# Connector.net
KiCad netlist of a schematic drawn in Altium Designer
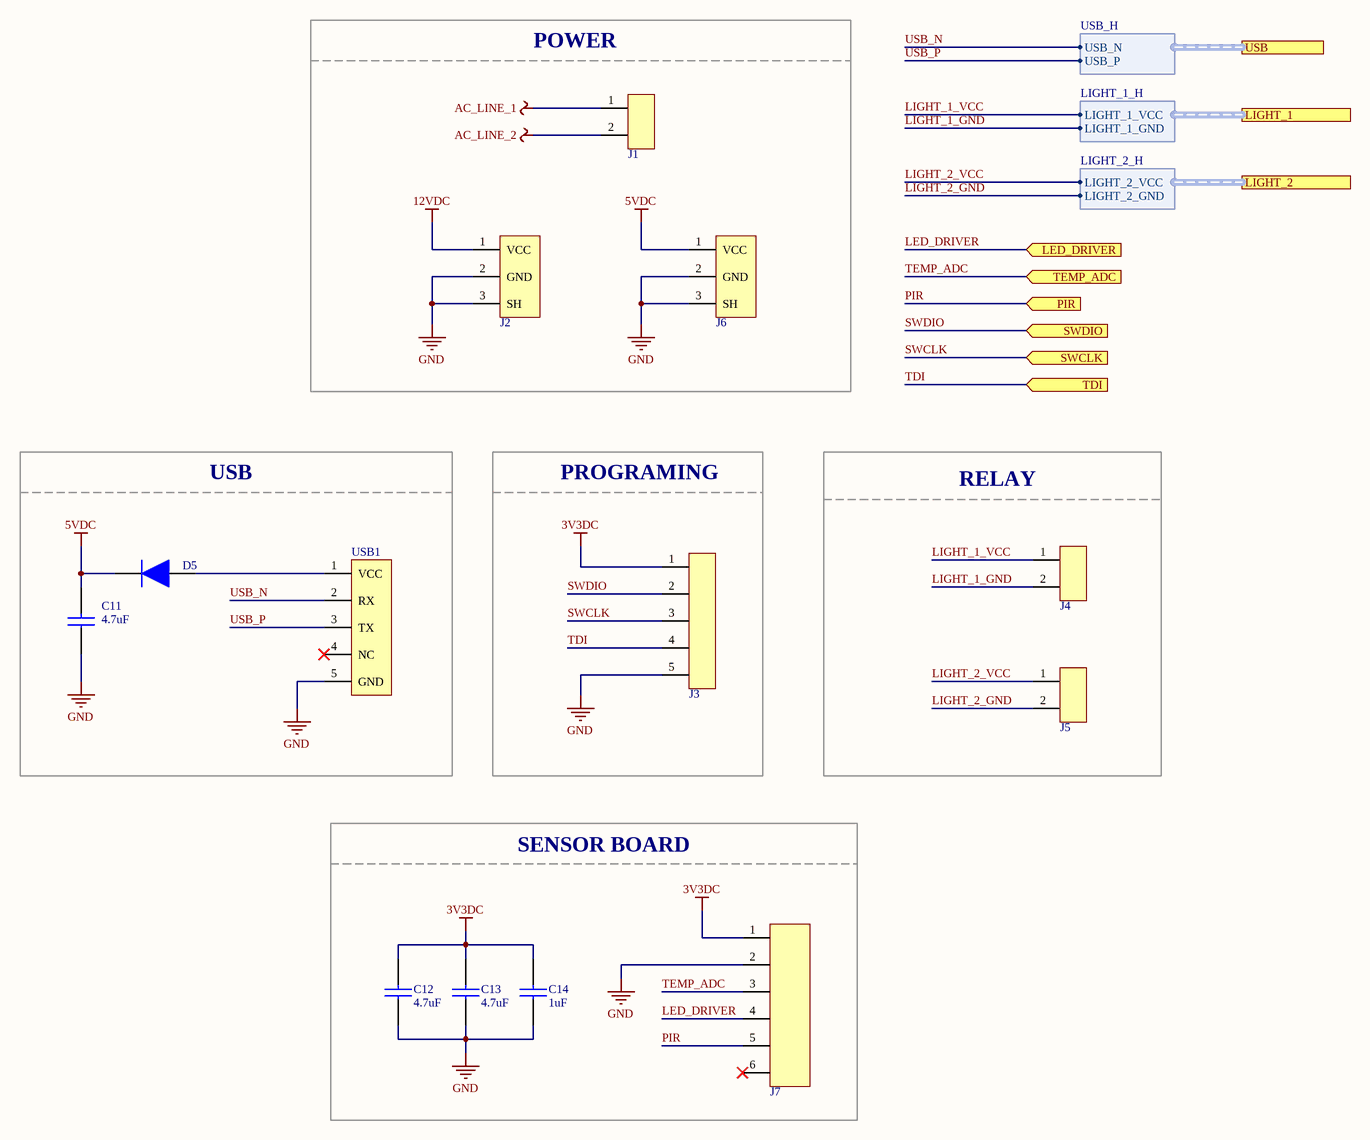
[diagram p0: Connector.SchDoc]

(export (version "E")
  (design (tool "Eeschema 10.0.6"))
  (components
    (comp (ref "C11")
      (value "CL21A475KAQNNNE")
      (footprint "CAP_0805")
      (description "CAP CER 4.7uF %10 0805")
      (fields
        (field (name "MANUFACTURER") "Samsung")
        (field (name "TOLERANCE") "10%")
        (field (name "CAPACITANCE") "4.7uF")
        (field (name "DESIGNED BY") "BERK")
      )
      (libsource (lib "GuvenlikSistemi_Library") (part "CAP CER 4.7uF 0805"))
    )
    (comp (ref "C12")
      (value "CL21A475KAQNNNE")
      (footprint "CAP_0805")
      (description "CAP CER 4.7uF %10 0805")
      (fields
        (field (name "MANUFACTURER") "Samsung")
        (field (name "TOLERANCE") "10%")
        (field (name "CAPACITANCE") "4.7uF")
        (field (name "DESIGNED BY") "BERK")
      )
      (libsource (lib "GuvenlikSistemi_Library") (part "CAP CER 4.7uF 0805"))
    )
    (comp (ref "C13")
      (value "CL21A475KAQNNNE")
      (footprint "CAP_0805")
      (description "CAP CER 4.7uF %10 0805")
      (fields
        (field (name "MANUFACTURER") "Samsung")
        (field (name "TOLERANCE") "10%")
        (field (name "CAPACITANCE") "4.7uF")
        (field (name "DESIGNED BY") "BERK")
      )
      (libsource (lib "GuvenlikSistemi_Library") (part "CAP CER 4.7uF 0805"))
    )
    (comp (ref "C14")
      (value "CL21B105KBFNNNE")
      (footprint "CAP_0805")
      (description "CAP CER 1uF %10 0805")
      (fields
        (field (name "MANUFACTURER") "Samsung")
        (field (name "TOLERANCE") "10%")
        (field (name "CAPACITANCE") "1uF")
        (field (name "DESIGNED BY") "BERK")
      )
      (libsource (lib "GuvenlikSistemi_Library") (part "CAP CER 1uF 0805"))
    )
    (comp (ref "D5")
      (value "1N4148WS")
      (footprint "SOD323F")
      (description "Diode, Single, 75 V, 150 mA, 1 V, 4 ns")
      (fields
        (field (name "MANUFACTURER") "ON Semiconductor / Fairchild")
        (field (name "DESIGNED BY") "BERK")
      )
      (libsource (lib "GuvenlikSistemi_Library") (part "1N4148WS"))
    )
    (comp (ref "J1")
      (value "TBP01R1-508-02BE")
      (footprint "TBP01R1-508")
      (description "Conn Shrouded Header HDR 2 POS 5.08mm Solder RA Side Entry Thru-Hole Bag")
      (fields (field (name "MANUFACTURER") "CUI") (field (name "DESIGNED BY") "BERK"))
      (libsource (lib "GuvenlikSistemi_Library") (part "TBP01R1-508-02BE"))
    )
    (comp (ref "J2")
      (value "PJ-037AH-SMT-TR")
      (footprint "JACK")
      (description "DC Power Connectors Power Jacks")
      (fields (field (name "MANUFACTURER") "CUI") (field (name "DESIGNED BY") "BERK"))
      (libsource (lib "GuvenlikSistemi_Library") (part "PJ-037AH-SMT-TR"))
    )
    (comp (ref "J3")
      (value "SMH-105-02-L-S")
      (footprint "PINHEADER1X5_RA")
      (description ".100 C.L. HORIZONTAL SMT SOCKET")
      (fields (field (name "MANUFACTURER") "Samtec") (field (name "DESIGNED BY") "BERK"))
      (libsource (lib "GuvenlikSistemi_Library") (part "SMH-105-02-L-S"))
    )
    (comp (ref "J4")
      (value "TBP01R1-508-02BE")
      (footprint "TBP01R1-508")
      (description "Conn Shrouded Header HDR 2 POS 5.08mm Solder RA Side Entry Thru-Hole Bag")
      (fields (field (name "MANUFACTURER") "CUI") (field (name "DESIGNED BY") "BERK"))
      (libsource (lib "GuvenlikSistemi_Library") (part "TBP01R1-508-02BE"))
    )
    (comp (ref "J5")
      (value "TBP01R1-508-02BE")
      (footprint "TBP01R1-508")
      (description "Conn Shrouded Header HDR 2 POS 5.08mm Solder RA Side Entry Thru-Hole Bag")
      (fields (field (name "MANUFACTURER") "CUI") (field (name "DESIGNED BY") "BERK"))
      (libsource (lib "GuvenlikSistemi_Library") (part "TBP01R1-508-02BE"))
    )
    (comp (ref "J6")
      (value "PJ-037AH-SMT-TR")
      (footprint "JACK")
      (description "DC Power Connectors Power Jacks")
      (fields (field (name "MANUFACTURER") "CUI") (field (name "DESIGNED BY") "BERK"))
      (libsource (lib "GuvenlikSistemi_Library") (part "PJ-037AH-SMT-TR"))
    )
    (comp (ref "J7")
      (value "64800611622")
      (footprint "64800611622")
      (description "1.50mm 6PIN Connector")
      (fields (field (name "MANUFACTURER") "Wurth Electronics"))
      (libsource (lib "GuvenlikSistemi_Library") (part "64800611622_conn_6pin"))
    )
    (comp (ref "USB1")
      (value "10118192-0001LF")
      (footprint "MICRO_B_USB")
      (description "CONN RCPT USB2.0 MICRO B SMD R/A")
      (fields (field (name "MANUFACTURER") "Amphenol FCI") (field (name "DESIGNED BY") "BERK"))
      (libsource (lib "GuvenlikSistemi_Library") (part "Micro B USB Connector"))
    )
  )
  (nets
    (net (code "4") (name "/LED_DRIVER") (class "Default") (node (ref "J7") (pin "4") (pintype "power_in")))
    (net (code "5") (name "/LIGHT_1_GND") (class "Default")
      (node (ref "J4") (pin "2") (pinfunction "2_2") (pintype "power_in"))
    )
    (net (code "6") (name "/LIGHT_1_VCC") (class "Default")
      (node (ref "J4") (pin "1") (pinfunction "1_1") (pintype "power_in"))
    )
    (net (code "7") (name "/LIGHT_2_GND") (class "Default")
      (node (ref "J5") (pin "2") (pinfunction "2_2") (pintype "power_in"))
    )
    (net (code "8") (name "/LIGHT_2_VCC") (class "Default")
      (node (ref "J5") (pin "1") (pinfunction "1_1") (pintype "power_in"))
    )
    (net (code "9") (name "/PIR") (class "Default") (node (ref "J7") (pin "5") (pintype "power_in")))
    (net (code "10") (name "/SWCLK") (class "Default")
      (node (ref "J3") (pin "3") (pinfunction "3_3") (pintype "power_in"))
    )
    (net (code "11") (name "/SWDIO") (class "Default")
      (node (ref "J3") (pin "2") (pinfunction "2_2") (pintype "power_in"))
    )
    (net (code "12") (name "/TDI") (class "Default")
      (node (ref "J3") (pin "4") (pinfunction "4_4") (pintype "power_in"))
    )
    (net (code "13") (name "/TEMP_ADC") (class "Default") (node (ref "J7") (pin "3") (pintype "power_in")))
    (net (code "14") (name "/USB_N") (class "Default")
      (node (ref "USB1") (pin "2") (pinfunction "RX_2") (pintype "power_in"))
    )
    (net (code "15") (name "/USB_P") (class "Default")
      (node (ref "USB1") (pin "3") (pinfunction "TX_3") (pintype "power_in"))
    )
    (net (code "19") (name "3V3DC") (class "Default")
      (node (ref "C12") (pin "2") (pinfunction "2_2") (pintype "passive"))
      (node (ref "C13") (pin "2") (pinfunction "2_2") (pintype "passive"))
      (node (ref "C14") (pin "2") (pinfunction "2_2") (pintype "passive"))
      (node (ref "J3") (pin "1") (pinfunction "1_1") (pintype "power_in"))
      (node (ref "J7") (pin "1") (pintype "power_in"))
    )
    (net (code "20") (name "5VDC") (class "Default")
      (node (ref "C11") (pin "2") (pinfunction "2_2") (pintype "passive"))
      (node (ref "D5") (pin "1") (pinfunction "1_1") (pintype "power_in"))
      (node (ref "J6") (pin "1") (pinfunction "VCC_1") (pintype "power_in"))
    )
    (net (code "21") (name "12VDC") (class "Default")
      (node (ref "J2") (pin "1") (pinfunction "VCC_1") (pintype "power_in"))
    )
    (net (code "22") (name "AC_LINE_1") (class "Default")
      (node (ref "J1") (pin "1") (pinfunction "1_1") (pintype "power_in"))
    )
    (net (code "23") (name "AC_LINE_2") (class "Default")
      (node (ref "J1") (pin "2") (pinfunction "2_2") (pintype "power_in"))
    )
    (net (code "24") (name "GND") (class "Default")
      (node (ref "C11") (pin "1") (pinfunction "1_1") (pintype "passive"))
      (node (ref "C12") (pin "1") (pinfunction "1_1") (pintype "passive"))
      (node (ref "C13") (pin "1") (pinfunction "1_1") (pintype "passive"))
      (node (ref "C14") (pin "1") (pinfunction "1_1") (pintype "passive"))
      (node (ref "J2") (pin "2") (pinfunction "GND_2") (pintype "power_in"))
      (node (ref "J2") (pin "3") (pinfunction "SH_3") (pintype "power_in"))
      (node (ref "J3") (pin "5") (pinfunction "5_5") (pintype "power_in"))
      (node (ref "J6") (pin "2") (pinfunction "GND_2") (pintype "power_in"))
      (node (ref "J6") (pin "3") (pinfunction "SH_3") (pintype "power_in"))
      (node (ref "J7") (pin "2") (pintype "power_in"))
      (node (ref "USB1") (pin "5") (pinfunction "GND_5") (pintype "power_in"))
    )
    (net (code "25") (name "Net-(USB1-VCC)") (class "Default")
      (node (ref "D5") (pin "2") (pinfunction "2_2") (pintype "power_in"))
      (node (ref "USB1") (pin "1") (pinfunction "VCC_1") (pintype "power_in"))
    )
    (net (code "26") (name "unconnected-(J7-Pad6)") (class "Default")
      (node (ref "J7") (pin "6") (pintype "power_in+no_connect"))
    )
    (net (code "27") (name "unconnected-(USB1-NC-Pad4)") (class "Default")
      (node (ref "USB1") (pin "4") (pinfunction "NC_4") (pintype "power_in+no_connect"))
    )
  )
)
